# IMU.net
KiCad netlist of a schematic drawn in Altium Designer
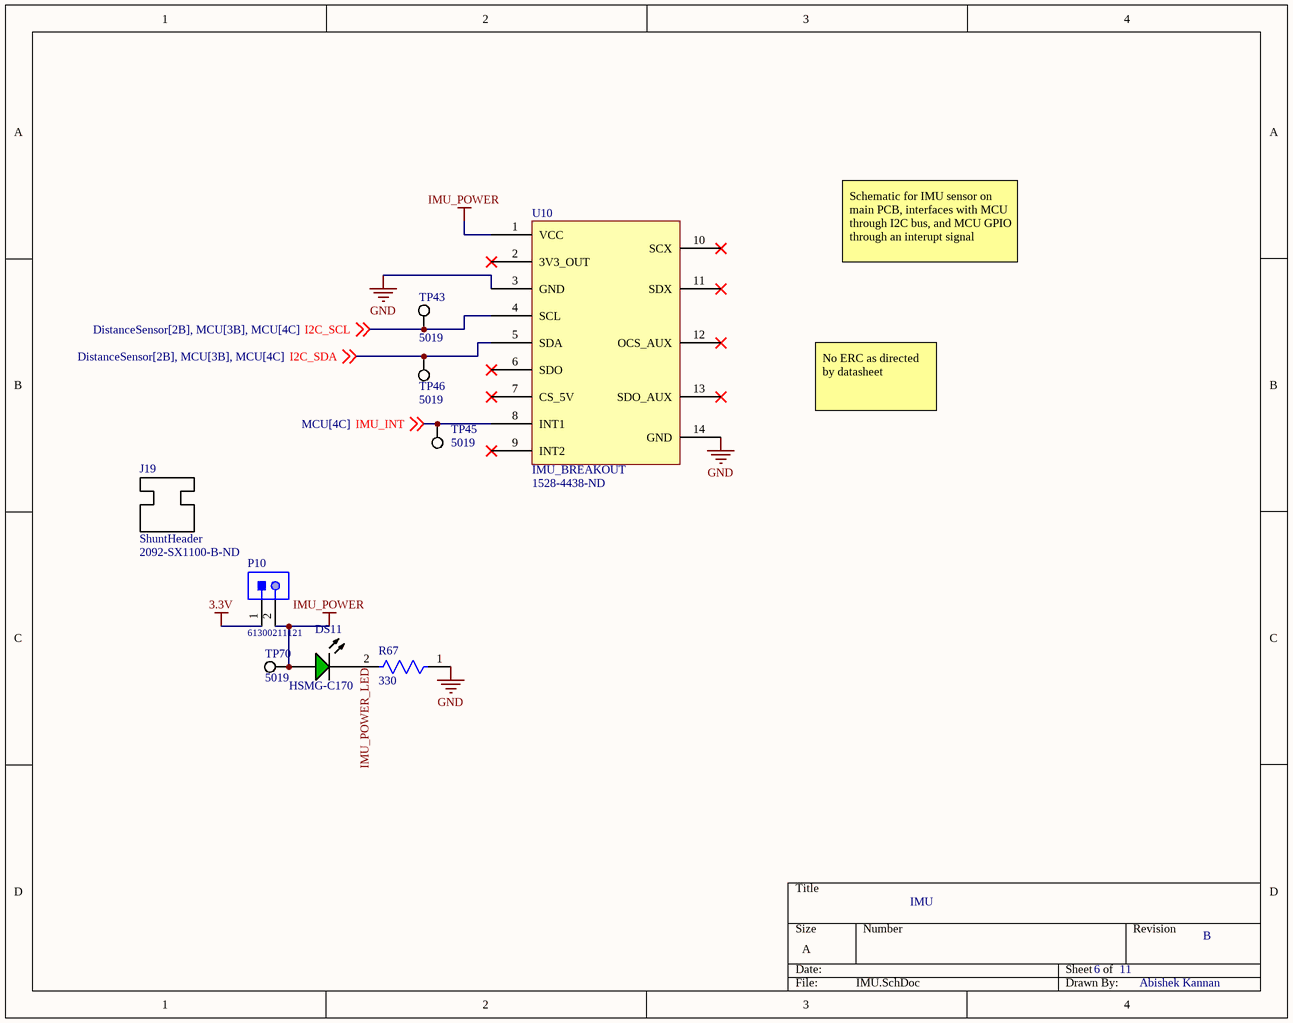
[diagram p0: IMU.SchDoc]

(export (version "E")
  (design (tool "Eeschema 10.0.6"))
  (components
    (comp (ref "DS11")
      (value "HSMG-C170")
      (footprint "AVAG-HSMX-C170_V")
      (description "Chip LED, Green, 2.2 V, -40 to 85 degC, 2-Pin SMD, Pb-Free, Tape and Reel")
      (fields (field (name "MANUFACTURER") "Avago"))
      (libsource (lib "Altium Content Vault") (part "LED_GREEN_A1K2-2"))
    )
    (comp (ref "J19")
      (value "ShuntHeader")
      (description "Conn Mini Shunt 2 POS 2.54mm Black Cable Mount")
      (fields
        (field (name "MANUFACTURER") "Kycon")
        (field (name "MANUFACTURER PART NUMBER") "SX1100-B")
        (field (name "SUPPLIER PART NUMBER 1") "2092-SX1100-B-ND")
      )
      (libsource (lib "CustomSchematics") (part "ShuntHeader"))
    )
    (comp (ref "P10")
      (value "61300211121")
      (footprint "61300211121")
      (description "THT Vertical Pin Header WR-PHD, Pitch 2.54 mm, Single Row, 2 pins")
      (fields (field (name "MANUFACTURER") "Wurth Elektronik") (field (name "PUBLISHER") "WurthElektronik"))
      (libsource (lib "Altium Content Vault") (part "WE-CN-1P-M-R2"))
    )
    (comp (ref "R67")
      (value "330")
      (footprint "FP-CRCW0805-e3-MFG")
      (description "RES Thick Film, 330Ω, 1%, 0.125W, 100ppm/°C, 0805")
      (fields (field (name "TOLERANCE") "1%") (field (name "MANUFACTURER") "Vishay"))
      (libsource (lib "Altium Content Vault") (part "1029c3af85768c4190bb7ad29bc67b5"))
    )
    (comp (ref "TP43")
      (value "5019")
      (footprint "KSTN-5019_V")
      (description "Test Point, 1 Position SMD, RoHS, Tape and Reel")
      (fields (field (name "MANUFACTURER") "Keystone Electronics"))
      (libsource (lib "Altium Content Vault") (part "TESTPOINT_WHITE"))
    )
    (comp (ref "TP45")
      (value "5019")
      (footprint "KSTN-5019_V")
      (description "Test Point, 1 Position SMD, RoHS, Tape and Reel")
      (fields (field (name "MANUFACTURER") "Keystone Electronics"))
      (libsource (lib "Altium Content Vault") (part "TESTPOINT_WHITE"))
    )
    (comp (ref "TP46")
      (value "5019")
      (footprint "KSTN-5019_V")
      (description "Test Point, 1 Position SMD, RoHS, Tape and Reel")
      (fields (field (name "MANUFACTURER") "Keystone Electronics"))
      (libsource (lib "Altium Content Vault") (part "TESTPOINT_WHITE"))
    )
    (comp (ref "TP70")
      (value "5019")
      (footprint "KSTN-5019_V")
      (description "Test Point, 1 Position SMD, RoHS, Tape and Reel")
      (fields (field (name "MANUFACTURER") "Keystone Electronics"))
      (libsource (lib "Altium Content Vault") (part "TESTPOINT_WHITE"))
    )
    (comp (ref "U10")
      (value "IMU_BREAKOUT")
      (footprint "IMU_BREAKOUT")
      (fields
        (field (name "MANUFACTURER") "Adafruit Industries")
        (field (name "MANUFACTURER PART NUMBER") "4438")
        (field (name "SUPPLIER PART NUMBER 1") "1528-4438-ND")
      )
      (libsource (lib "CustomSchematics") (part "IMU_BREAKOUT"))
    )
  )
  (nets
    (net (code "1") (name "/IMU_POWER_LED") (class "Default")
      (node (ref "DS11") (pin "2") (pinfunction "K_2") (pintype "passive"))
      (node (ref "R67") (pin "2") (pinfunction "2_2") (pintype "passive"))
    )
    (net (code "2") (name "3.3V") (class "Default")
      (node (ref "P10") (pin "1") (pinfunction "1_1") (pintype "passive"))
    )
    (net (code "3") (name "GND") (class "Default")
      (node (ref "R67") (pin "1") (pinfunction "1_1") (pintype "passive"))
      (node (ref "U10") (pin "14") (pinfunction "GND_14") (pintype "passive"))
      (node (ref "U10") (pin "3") (pinfunction "GND_3") (pintype "passive"))
    )
    (net (code "4") (name "I2C_SCL") (class "Default")
      (node (ref "TP43") (pin "1") (pinfunction "1_1") (pintype "passive"))
      (node (ref "U10") (pin "4") (pinfunction "SCL_4") (pintype "passive"))
    )
    (net (code "5") (name "I2C_SDA") (class "Default")
      (node (ref "TP46") (pin "1") (pinfunction "1_1") (pintype "passive"))
      (node (ref "U10") (pin "5") (pinfunction "SDA_5") (pintype "passive"))
    )
    (net (code "6") (name "IMU_INT") (class "Default")
      (node (ref "TP45") (pin "1") (pinfunction "1_1") (pintype "passive"))
      (node (ref "U10") (pin "8") (pinfunction "INT1_8") (pintype "passive"))
    )
    (net (code "7") (name "IMU_POWER") (class "Default")
      (node (ref "DS11") (pin "1") (pinfunction "A_1") (pintype "passive"))
      (node (ref "P10") (pin "2") (pinfunction "2_2") (pintype "passive"))
      (node (ref "TP70") (pin "1") (pinfunction "1_1") (pintype "passive"))
      (node (ref "U10") (pin "1") (pinfunction "VCC_1") (pintype "passive"))
    )
    (net (code "8") (name "unconnected-(U10-3V3_OUT-Pad2)") (class "Default")
      (node (ref "U10") (pin "2") (pinfunction "3V3_OUT_2") (pintype "passive+no_connect"))
    )
    (net (code "9") (name "unconnected-(U10-CS_5V-Pad7)") (class "Default")
      (node (ref "U10") (pin "7") (pinfunction "CS_5V_7") (pintype "passive+no_connect"))
    )
    (net (code "10") (name "unconnected-(U10-INT2-Pad9)") (class "Default")
      (node (ref "U10") (pin "9") (pinfunction "INT2_9") (pintype "passive+no_connect"))
    )
    (net (code "11") (name "unconnected-(U10-OCS_AUX-Pad12)") (class "Default")
      (node (ref "U10") (pin "12") (pinfunction "OCS_AUX_12") (pintype "passive+no_connect"))
    )
    (net (code "12") (name "unconnected-(U10-SCX-Pad10)") (class "Default")
      (node (ref "U10") (pin "10") (pinfunction "SCX_10") (pintype "passive+no_connect"))
    )
    (net (code "13") (name "unconnected-(U10-SDO-Pad6)") (class "Default")
      (node (ref "U10") (pin "6") (pinfunction "SDO_6") (pintype "passive+no_connect"))
    )
    (net (code "14") (name "unconnected-(U10-SDO_AUX-Pad13)") (class "Default")
      (node (ref "U10") (pin "13") (pinfunction "SDO_AUX_13") (pintype "passive+no_connect"))
    )
    (net (code "15") (name "unconnected-(U10-SDX-Pad11)") (class "Default")
      (node (ref "U10") (pin "11") (pinfunction "SDX_11") (pintype "passive+no_connect"))
    )
  )
)
